# M220p16.net
KiCad netlist of a schematic drawn in EAGLE
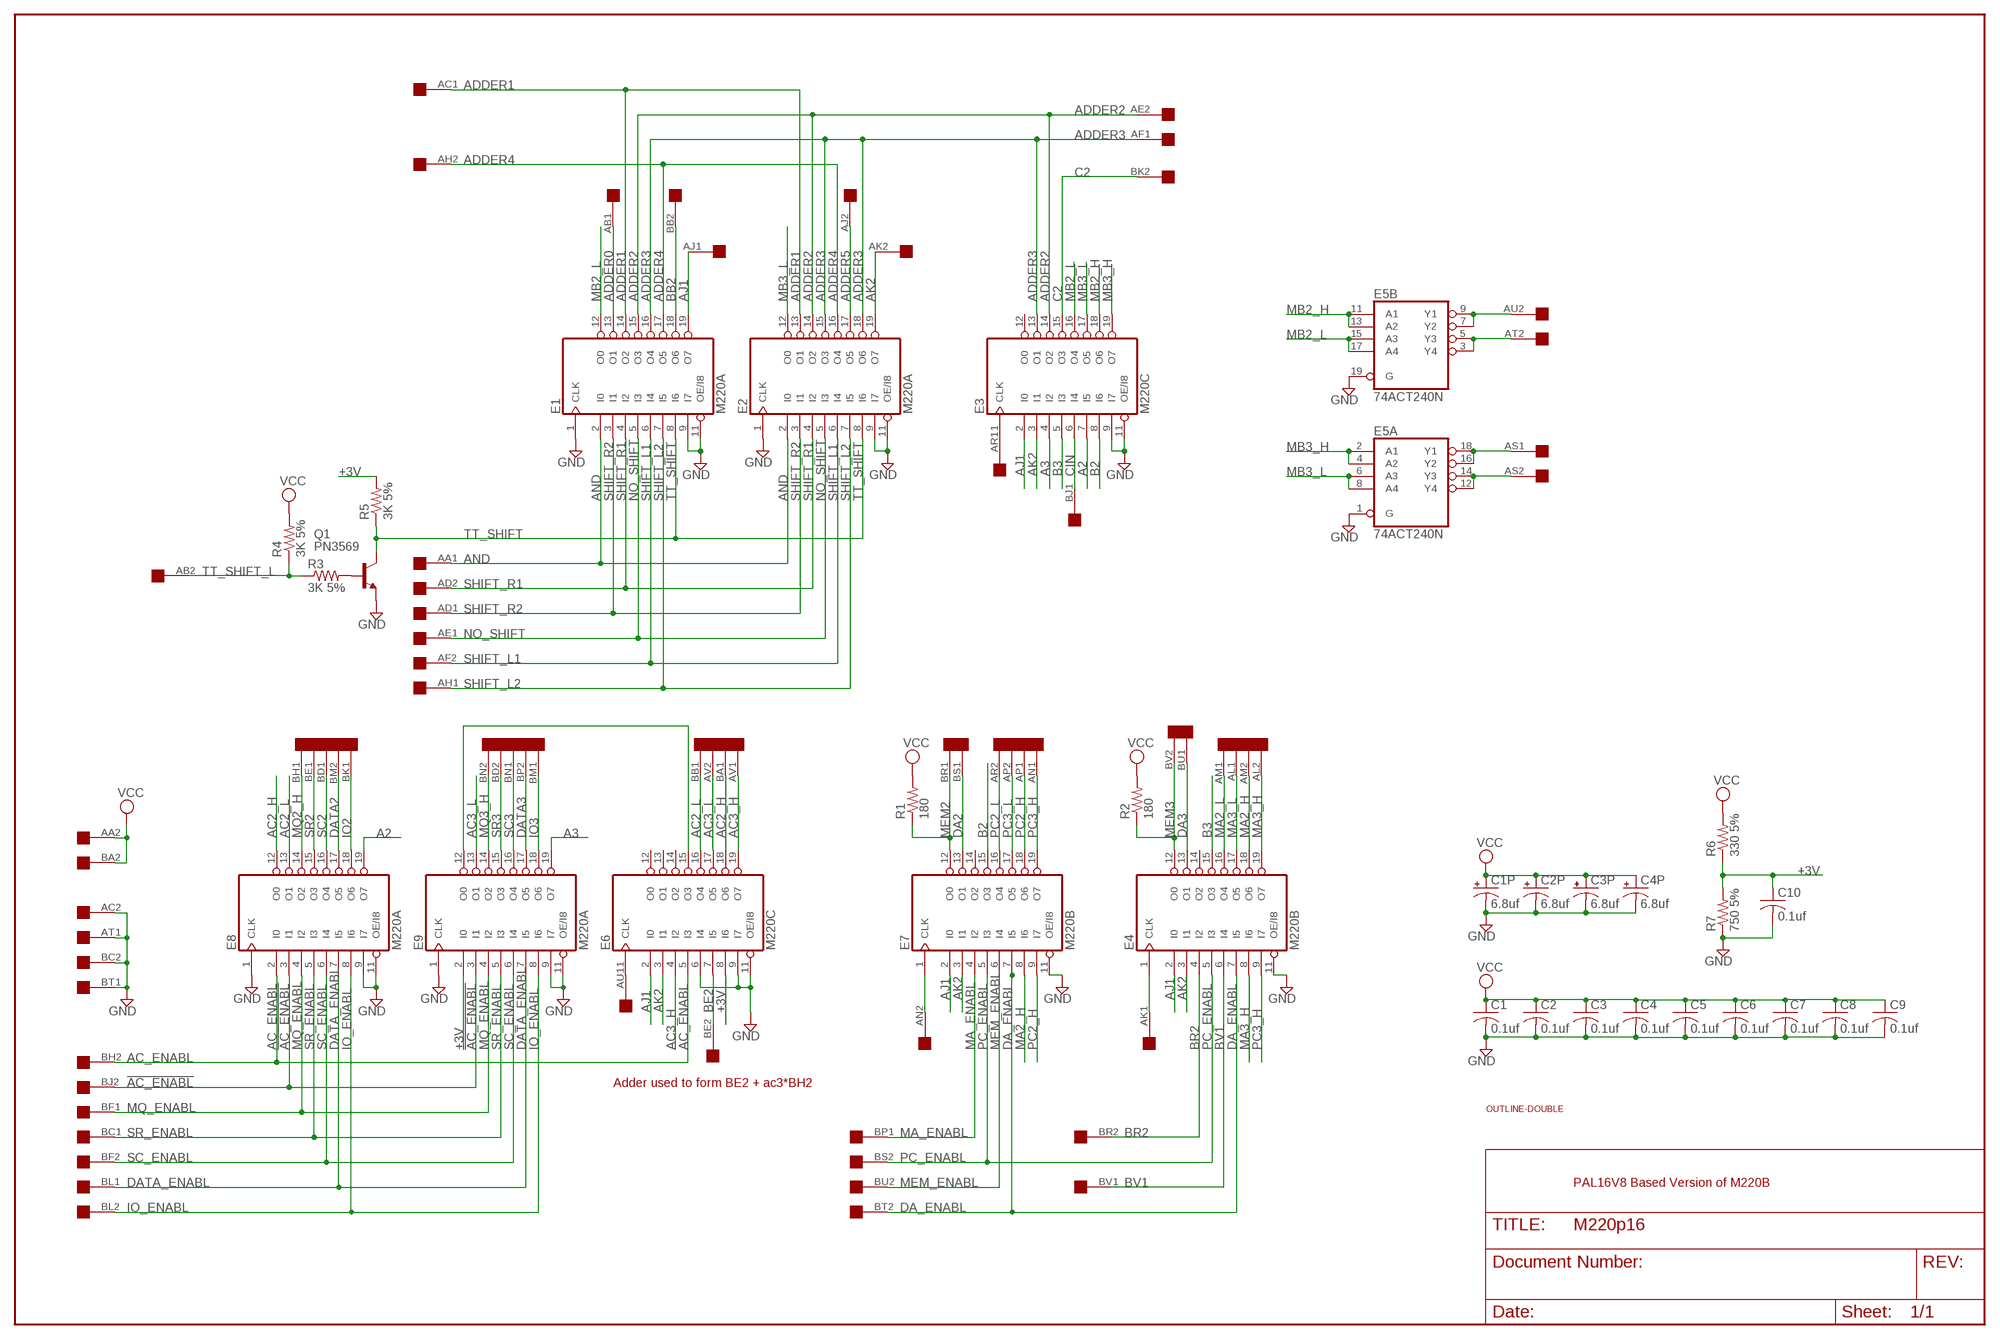
[diagram p0: schematic, sheet 1]

(export (version "E")
  (design (tool "Eeschema 10.0.6"))
  (components
    (comp (ref "C1")
      (value "0.1uf")
      (footprint "eagle-import:C050-025X075")
      (libsource (lib "eagle-import") (part "C-US050-025X075"))
    )
    (comp (ref "C1P")
      (value "6.8uf")
      (footprint "eagle-import:E15-5")
      (libsource (lib "eagle-import") (part "CPOL-USE15-5AXIAL"))
    )
    (comp (ref "C2")
      (value "0.1uf")
      (footprint "eagle-import:C050-025X075")
      (libsource (lib "eagle-import") (part "C-US050-025X075"))
    )
    (comp (ref "C2P")
      (value "6.8uf")
      (footprint "eagle-import:E15-5")
      (libsource (lib "eagle-import") (part "CPOL-USE15-5AXIAL"))
    )
    (comp (ref "C3")
      (value "0.1uf")
      (footprint "eagle-import:C050-025X075")
      (libsource (lib "eagle-import") (part "C-US050-025X075"))
    )
    (comp (ref "C3P")
      (value "6.8uf")
      (footprint "eagle-import:E15-5")
      (libsource (lib "eagle-import") (part "CPOL-USE15-5AXIAL"))
    )
    (comp (ref "C4")
      (value "0.1uf")
      (footprint "eagle-import:C050-025X075")
      (libsource (lib "eagle-import") (part "C-US050-025X075"))
    )
    (comp (ref "C4P")
      (value "6.8uf")
      (footprint "eagle-import:E15-5")
      (libsource (lib "eagle-import") (part "CPOL-USE15-5AXIAL"))
    )
    (comp (ref "C5")
      (value "0.1uf")
      (footprint "eagle-import:C050-025X075")
      (libsource (lib "eagle-import") (part "C-US050-025X075"))
    )
    (comp (ref "C6")
      (value "0.1uf")
      (footprint "eagle-import:C050-025X075")
      (libsource (lib "eagle-import") (part "C-US050-025X075"))
    )
    (comp (ref "C7")
      (value "0.1uf")
      (footprint "eagle-import:C050-025X075")
      (libsource (lib "eagle-import") (part "C-US050-025X075"))
    )
    (comp (ref "C8")
      (value "0.1uf")
      (footprint "eagle-import:C050-025X075")
      (libsource (lib "eagle-import") (part "C-US050-025X075"))
    )
    (comp (ref "C9")
      (value "0.1uf")
      (footprint "eagle-import:C050-025X075")
      (libsource (lib "eagle-import") (part "C-US050-025X075"))
    )
    (comp (ref "C10")
      (value "0.1uf")
      (footprint "eagle-import:C050-025X075")
      (libsource (lib "eagle-import") (part "C-US050-025X075"))
    )
    (comp (ref "E1")
      (value "M220A")
      (footprint "eagle-import:DIL20")
      (fields (field (name "MPN") "GAL16V8D-7LPN"))
      (libsource (lib "eagle-import") (part "16V8"))
    )
    (comp (ref "E2")
      (value "M220A")
      (footprint "eagle-import:DIL20")
      (fields (field (name "MPN") "GAL16V8D-7LPN"))
      (libsource (lib "eagle-import") (part "16V8"))
    )
    (comp (ref "E3")
      (value "M220C")
      (footprint "eagle-import:DIL20")
      (fields (field (name "MPN") "GAL16V8D-7LPN"))
      (libsource (lib "eagle-import") (part "16V8"))
    )
    (comp (ref "E4")
      (value "M220B")
      (footprint "eagle-import:DIL20")
      (fields (field (name "MPN") "GAL16V8D-7LPN"))
      (libsource (lib "eagle-import") (part "16V8"))
    )
    (comp (ref "E5")
      (value "74ACT240N")
      (footprint "eagle-import:DIL20")
      (libsource (lib "eagle-import") (part "74240NS"))
    )
    (comp (ref "E6")
      (value "M220C")
      (footprint "eagle-import:DIL20")
      (fields (field (name "MPN") "GAL16V8D-7LPN"))
      (libsource (lib "eagle-import") (part "16V8"))
    )
    (comp (ref "E7")
      (value "M220B")
      (footprint "eagle-import:DIL20")
      (fields (field (name "MPN") "GAL16V8D-7LPN"))
      (libsource (lib "eagle-import") (part "16V8"))
    )
    (comp (ref "E8")
      (value "M220A")
      (footprint "eagle-import:DIL20")
      (fields (field (name "MPN") "GAL16V8D-7LPN"))
      (libsource (lib "eagle-import") (part "16V8"))
    )
    (comp (ref "E9")
      (value "M220A")
      (footprint "eagle-import:DIL20")
      (fields (field (name "MPN") "GAL16V8D-7LPN"))
      (libsource (lib "eagle-import") (part "16V8"))
    )
    (comp (ref "Q1")
      (value "PN3569")
      (footprint "eagle-import:TO5")
      (libsource (lib "eagle-import") (part "2N2102"))
    )
    (comp (ref "R1")
      (value "180")
      (footprint "eagle-import:0207_10")
      (libsource (lib "eagle-import") (part "R-US_0207/10"))
    )
    (comp (ref "R2")
      (value "180")
      (footprint "eagle-import:0207_10")
      (libsource (lib "eagle-import") (part "R-US_0207/10"))
    )
    (comp (ref "R3")
      (value "3K 5%")
      (footprint "eagle-import:0207_10")
      (libsource (lib "eagle-import") (part "R-US_0207/10"))
    )
    (comp (ref "R4")
      (value "3K 5%")
      (footprint "eagle-import:0207_10")
      (libsource (lib "eagle-import") (part "R-US_0207/10"))
    )
    (comp (ref "R5")
      (value "3K 5%")
      (footprint "eagle-import:0207_10")
      (libsource (lib "eagle-import") (part "R-US_0207/10"))
    )
    (comp (ref "R6")
      (value "330 5%")
      (footprint "eagle-import:0207_10")
      (libsource (lib "eagle-import") (part "R-US_0207/10"))
    )
    (comp (ref "R7")
      (value "750 5%")
      (footprint "eagle-import:0207_10")
      (libsource (lib "eagle-import") (part "R-US_0207/10"))
    )
    (comp (ref "U$1")
      (value "DOUBLE")
      (footprint "eagle-import:EDGE-CON4")
      (libsource (lib "eagle-import") (part "DOUBLE"))
    )
    (comp (ref "U$2")
      (value "OUTLINE-DOUBLE")
      (footprint "eagle-import:DOUBLE")
      (libsource (lib "eagle-import") (part "OUTLINE-DOUBLE"))
    )
  )
  (nets
    (net (code "1") (name "/+3V") (class "Default")
      (node (ref "C10") (pin "1") (pinfunction "1_1") (pintype "passive"))
      (node (ref "E6") (pin "8") (pinfunction "I6_8") (pintype "input"))
      (node (ref "E9") (pin "2") (pinfunction "I0_2") (pintype "input"))
      (node (ref "R5") (pin "2") (pinfunction "2_2") (pintype "passive"))
      (node (ref "R6") (pin "1") (pinfunction "1_1") (pintype "passive"))
      (node (ref "R7") (pin "2") (pinfunction "2_2") (pintype "passive"))
    )
    (net (code "2") (name "/A2") (class "Default")
      (node (ref "E3") (pin "7") (pinfunction "I5_7") (pintype "input"))
      (node (ref "E8") (pin "19") (pinfunction "O7_19") (pintype "bidirectional"))
    )
    (net (code "3") (name "/A3") (class "Default")
      (node (ref "E3") (pin "4") (pinfunction "I2_4") (pintype "input"))
      (node (ref "E9") (pin "19") (pinfunction "O7_19") (pintype "bidirectional"))
    )
    (net (code "4") (name "/AC2_H") (class "Default")
      (node (ref "E6") (pin "18") (pinfunction "O6_18") (pintype "bidirectional"))
      (node (ref "E8") (pin "12") (pinfunction "O0_12") (pintype "bidirectional"))
      (node (ref "U$1") (pin "BA1") (pinfunction "1_BA1") (pintype "bidirectional"))
    )
    (net (code "5") (name "/AC2_L") (class "Default")
      (node (ref "E6") (pin "16") (pinfunction "O4_16") (pintype "bidirectional"))
      (node (ref "E8") (pin "13") (pinfunction "O1_13") (pintype "bidirectional"))
      (node (ref "U$1") (pin "BB1") (pinfunction "1_BB1") (pintype "bidirectional"))
    )
    (net (code "6") (name "/AC3_H") (class "Default")
      (node (ref "E6") (pin "19") (pinfunction "O7_19") (pintype "bidirectional"))
      (node (ref "E6") (pin "4") (pinfunction "I2_4") (pintype "input"))
      (node (ref "U$1") (pin "AV1") (pinfunction "1_AV1") (pintype "bidirectional"))
    )
    (net (code "7") (name "/AC3_L") (class "Default")
      (node (ref "E6") (pin "17") (pinfunction "O5_17") (pintype "bidirectional"))
      (node (ref "E9") (pin "13") (pinfunction "O1_13") (pintype "bidirectional"))
      (node (ref "U$1") (pin "AV2") (pinfunction "1_AV2") (pintype "bidirectional"))
    )
    (net (code "8") (name "/AC_ENABL") (class "Default")
      (node (ref "E6") (pin "5") (pinfunction "I3_5") (pintype "input"))
      (node (ref "E8") (pin "2") (pinfunction "I0_2") (pintype "input"))
      (node (ref "U$1") (pin "BH2") (pinfunction "1_BH2") (pintype "bidirectional"))
    )
    (net (code "9") (name "/ADDER0") (class "Default")
      (node (ref "E1") (pin "13") (pinfunction "O1_13") (pintype "bidirectional"))
      (node (ref "U$1") (pin "AB1") (pinfunction "1_AB1") (pintype "bidirectional"))
    )
    (net (code "10") (name "/ADDER1") (class "Default")
      (node (ref "E1") (pin "14") (pinfunction "O2_14") (pintype "bidirectional"))
      (node (ref "E2") (pin "13") (pinfunction "O1_13") (pintype "bidirectional"))
      (node (ref "U$1") (pin "AC1") (pinfunction "1_AC1") (pintype "bidirectional"))
    )
    (net (code "11") (name "/ADDER2") (class "Default")
      (node (ref "E1") (pin "15") (pinfunction "O3_15") (pintype "bidirectional"))
      (node (ref "E2") (pin "14") (pinfunction "O2_14") (pintype "bidirectional"))
      (node (ref "E3") (pin "14") (pinfunction "O2_14") (pintype "bidirectional"))
      (node (ref "U$1") (pin "AE2") (pinfunction "1_AE2") (pintype "bidirectional"))
    )
    (net (code "12") (name "/ADDER3") (class "Default")
      (node (ref "E1") (pin "16") (pinfunction "O4_16") (pintype "bidirectional"))
      (node (ref "E2") (pin "15") (pinfunction "O3_15") (pintype "bidirectional"))
      (node (ref "E2") (pin "18") (pinfunction "O6_18") (pintype "bidirectional"))
      (node (ref "E3") (pin "13") (pinfunction "O1_13") (pintype "bidirectional"))
      (node (ref "U$1") (pin "AF1") (pinfunction "1_AF1") (pintype "bidirectional"))
    )
    (net (code "13") (name "/ADDER4") (class "Default")
      (node (ref "E1") (pin "17") (pinfunction "O5_17") (pintype "bidirectional"))
      (node (ref "E2") (pin "16") (pinfunction "O4_16") (pintype "bidirectional"))
      (node (ref "U$1") (pin "AH2") (pinfunction "1_AH2") (pintype "bidirectional"))
    )
    (net (code "14") (name "/ADDER5") (class "Default")
      (node (ref "E2") (pin "17") (pinfunction "O5_17") (pintype "bidirectional"))
      (node (ref "U$1") (pin "AJ2") (pinfunction "1_AJ2") (pintype "bidirectional"))
    )
    (net (code "15") (name "/AJ1") (class "Default")
      (node (ref "E1") (pin "19") (pinfunction "O7_19") (pintype "bidirectional"))
      (node (ref "E3") (pin "2") (pinfunction "I0_2") (pintype "input"))
      (node (ref "E4") (pin "2") (pinfunction "I0_2") (pintype "input"))
      (node (ref "E6") (pin "2") (pinfunction "I0_2") (pintype "input"))
      (node (ref "E7") (pin "2") (pinfunction "I0_2") (pintype "input"))
      (node (ref "U$1") (pin "AJ1") (pinfunction "1_AJ1") (pintype "bidirectional"))
    )
    (net (code "16") (name "/AK2") (class "Default")
      (node (ref "E2") (pin "19") (pinfunction "O7_19") (pintype "bidirectional"))
      (node (ref "E3") (pin "3") (pinfunction "I1_3") (pintype "input"))
      (node (ref "E4") (pin "3") (pinfunction "I1_3") (pintype "input"))
      (node (ref "E6") (pin "3") (pinfunction "I1_3") (pintype "input"))
      (node (ref "E7") (pin "3") (pinfunction "I1_3") (pintype "input"))
      (node (ref "U$1") (pin "AK2") (pinfunction "1_AK2") (pintype "bidirectional"))
    )
    (net (code "17") (name "/AND") (class "Default")
      (node (ref "E1") (pin "2") (pinfunction "I0_2") (pintype "input"))
      (node (ref "E2") (pin "2") (pinfunction "I0_2") (pintype "input"))
      (node (ref "U$1") (pin "AA1") (pinfunction "1_AA1") (pintype "bidirectional"))
    )
    (net (code "18") (name "/B2") (class "Default")
      (node (ref "E3") (pin "8") (pinfunction "I6_8") (pintype "input"))
      (node (ref "E7") (pin "15") (pinfunction "O3_15") (pintype "bidirectional"))
    )
    (net (code "19") (name "/B3") (class "Default")
      (node (ref "E3") (pin "5") (pinfunction "I3_5") (pintype "input"))
      (node (ref "E4") (pin "15") (pinfunction "O3_15") (pintype "bidirectional"))
    )
    (net (code "20") (name "/BB2") (class "Default")
      (node (ref "E1") (pin "18") (pinfunction "O6_18") (pintype "bidirectional"))
      (node (ref "U$1") (pin "BB2") (pinfunction "1_BB2") (pintype "bidirectional"))
    )
    (net (code "21") (name "/BE2") (class "Default")
      (node (ref "E6") (pin "7") (pinfunction "I5_7") (pintype "input"))
      (node (ref "U$1") (pin "BE2") (pinfunction "1_BE2") (pintype "bidirectional"))
    )
    (net (code "22") (name "/BR2") (class "Default")
      (node (ref "E4") (pin "4") (pinfunction "I2_4") (pintype "input"))
      (node (ref "U$1") (pin "BR2") (pinfunction "1_BR2") (pintype "bidirectional"))
    )
    (net (code "23") (name "/BV1") (class "Default")
      (node (ref "E4") (pin "6") (pinfunction "I4_6") (pintype "input"))
      (node (ref "U$1") (pin "BV1") (pinfunction "1_BV1") (pintype "bidirectional"))
    )
    (net (code "24") (name "/C2") (class "Default")
      (node (ref "E3") (pin "15") (pinfunction "O3_15") (pintype "bidirectional"))
      (node (ref "U$1") (pin "BK2") (pinfunction "1_BK2") (pintype "bidirectional"))
    )
    (net (code "25") (name "/CIN") (class "Default")
      (node (ref "E3") (pin "6") (pinfunction "I4_6") (pintype "input"))
      (node (ref "U$1") (pin "BJ1") (pinfunction "1_BJ1") (pintype "bidirectional"))
    )
    (net (code "26") (name "/DA2") (class "Default")
      (node (ref "E7") (pin "13") (pinfunction "O1_13") (pintype "bidirectional"))
      (node (ref "U$1") (pin "BS1") (pinfunction "1_BS1") (pintype "bidirectional"))
    )
    (net (code "27") (name "/DA3") (class "Default")
      (node (ref "E4") (pin "13") (pinfunction "O1_13") (pintype "bidirectional"))
      (node (ref "U$1") (pin "BU1") (pinfunction "1_BU1") (pintype "bidirectional"))
    )
    (net (code "28") (name "/DATA2") (class "Default")
      (node (ref "E8") (pin "17") (pinfunction "O5_17") (pintype "bidirectional"))
      (node (ref "U$1") (pin "BM2") (pinfunction "1_BM2") (pintype "bidirectional"))
    )
    (net (code "29") (name "/DATA3") (class "Default")
      (node (ref "E9") (pin "17") (pinfunction "O5_17") (pintype "bidirectional"))
      (node (ref "U$1") (pin "BP2") (pinfunction "1_BP2") (pintype "bidirectional"))
    )
    (net (code "30") (name "/DATA_ENABL") (class "Default")
      (node (ref "E8") (pin "7") (pinfunction "I5_7") (pintype "input"))
      (node (ref "E9") (pin "7") (pinfunction "I5_7") (pintype "input"))
      (node (ref "U$1") (pin "BL1") (pinfunction "1_BL1") (pintype "bidirectional"))
    )
    (net (code "31") (name "/DA_ENABL") (class "Default")
      (node (ref "E4") (pin "7") (pinfunction "I5_7") (pintype "input"))
      (node (ref "E7") (pin "7") (pinfunction "I5_7") (pintype "input"))
      (node (ref "U$1") (pin "BT2") (pinfunction "1_BT2") (pintype "bidirectional"))
    )
    (net (code "32") (name "/IO2") (class "Default")
      (node (ref "E8") (pin "18") (pinfunction "O6_18") (pintype "bidirectional"))
      (node (ref "U$1") (pin "BK1") (pinfunction "1_BK1") (pintype "bidirectional"))
    )
    (net (code "33") (name "/IO3") (class "Default")
      (node (ref "E9") (pin "18") (pinfunction "O6_18") (pintype "bidirectional"))
      (node (ref "U$1") (pin "BM1") (pinfunction "1_BM1") (pintype "bidirectional"))
    )
    (net (code "34") (name "/IO_ENABL") (class "Default")
      (node (ref "E8") (pin "8") (pinfunction "I6_8") (pintype "input"))
      (node (ref "E9") (pin "8") (pinfunction "I6_8") (pintype "input"))
      (node (ref "U$1") (pin "BL2") (pinfunction "1_BL2") (pintype "bidirectional"))
    )
    (net (code "35") (name "/MA2_H") (class "Default")
      (node (ref "E4") (pin "18") (pinfunction "O6_18") (pintype "bidirectional"))
      (node (ref "E7") (pin "8") (pinfunction "I6_8") (pintype "input"))
      (node (ref "U$1") (pin "AM2") (pinfunction "1_AM2") (pintype "bidirectional"))
    )
    (net (code "36") (name "/MA2_L") (class "Default")
      (node (ref "E4") (pin "16") (pinfunction "O4_16") (pintype "bidirectional"))
      (node (ref "U$1") (pin "AM1") (pinfunction "1_AM1") (pintype "bidirectional"))
    )
    (net (code "37") (name "/MA3_H") (class "Default")
      (node (ref "E4") (pin "19") (pinfunction "O7_19") (pintype "bidirectional"))
      (node (ref "E4") (pin "8") (pinfunction "I6_8") (pintype "input"))
      (node (ref "U$1") (pin "AL2") (pinfunction "1_AL2") (pintype "bidirectional"))
    )
    (net (code "38") (name "/MA3_L") (class "Default")
      (node (ref "E4") (pin "17") (pinfunction "O5_17") (pintype "bidirectional"))
      (node (ref "U$1") (pin "AL1") (pinfunction "1_AL1") (pintype "bidirectional"))
    )
    (net (code "39") (name "/MA_ENABL") (class "Default")
      (node (ref "E7") (pin "4") (pinfunction "I2_4") (pintype "input"))
      (node (ref "U$1") (pin "BP1") (pinfunction "1_BP1") (pintype "bidirectional"))
    )
    (net (code "40") (name "/MB2_H") (class "Default")
      (node (ref "E3") (pin "18") (pinfunction "O6_18") (pintype "bidirectional"))
      (node (ref "E5") (pin "11") (pinfunction "A1_11") (pintype "input"))
      (node (ref "E5") (pin "13") (pinfunction "A2_13") (pintype "input"))
    )
    (net (code "41") (name "/MB2_L") (class "Default")
      (node (ref "E1") (pin "12") (pinfunction "O0_12") (pintype "bidirectional"))
      (node (ref "E3") (pin "16") (pinfunction "O4_16") (pintype "bidirectional"))
      (node (ref "E5") (pin "15") (pinfunction "A3_15") (pintype "input"))
      (node (ref "E5") (pin "17") (pinfunction "A4_17") (pintype "input"))
    )
    (net (code "42") (name "/MB3_H") (class "Default")
      (node (ref "E3") (pin "19") (pinfunction "O7_19") (pintype "bidirectional"))
      (node (ref "E5") (pin "2") (pinfunction "A1_2") (pintype "input"))
      (node (ref "E5") (pin "4") (pinfunction "A2_4") (pintype "input"))
    )
    (net (code "43") (name "/MB3_L") (class "Default")
      (node (ref "E2") (pin "12") (pinfunction "O0_12") (pintype "bidirectional"))
      (node (ref "E3") (pin "17") (pinfunction "O5_17") (pintype "bidirectional"))
      (node (ref "E5") (pin "6") (pinfunction "A3_6") (pintype "input"))
      (node (ref "E5") (pin "8") (pinfunction "A4_8") (pintype "input"))
    )
    (net (code "44") (name "/MEM2") (class "Default")
      (node (ref "E7") (pin "12") (pinfunction "O0_12") (pintype "bidirectional"))
      (node (ref "R1") (pin "1") (pinfunction "1_1") (pintype "passive"))
      (node (ref "U$1") (pin "BR1") (pinfunction "1_BR1") (pintype "bidirectional"))
    )
    (net (code "45") (name "/MEM3") (class "Default")
      (node (ref "E4") (pin "12") (pinfunction "O0_12") (pintype "bidirectional"))
      (node (ref "R2") (pin "1") (pinfunction "1_1") (pintype "passive"))
      (node (ref "U$1") (pin "BV2") (pinfunction "1_BV2") (pintype "bidirectional"))
    )
    (net (code "46") (name "/MEM_ENABL") (class "Default")
      (node (ref "E7") (pin "6") (pinfunction "I4_6") (pintype "input"))
      (node (ref "U$1") (pin "BU2") (pinfunction "1_BU2") (pintype "bidirectional"))
    )
    (net (code "47") (name "/MQ2_H") (class "Default")
      (node (ref "E8") (pin "14") (pinfunction "O2_14") (pintype "bidirectional"))
      (node (ref "U$1") (pin "BH1") (pinfunction "1_BH1") (pintype "bidirectional"))
    )
    (net (code "48") (name "/MQ3_H") (class "Default")
      (node (ref "E9") (pin "14") (pinfunction "O2_14") (pintype "bidirectional"))
      (node (ref "U$1") (pin "BN2") (pinfunction "1_BN2") (pintype "bidirectional"))
    )
    (net (code "49") (name "/MQ_ENABL") (class "Default")
      (node (ref "E8") (pin "4") (pinfunction "I2_4") (pintype "input"))
      (node (ref "E9") (pin "4") (pinfunction "I2_4") (pintype "input"))
      (node (ref "U$1") (pin "BF1") (pinfunction "1_BF1") (pintype "bidirectional"))
    )
    (net (code "50") (name "/NO_SHIFT") (class "Default")
      (node (ref "E1") (pin "5") (pinfunction "I3_5") (pintype "input"))
      (node (ref "E2") (pin "5") (pinfunction "I3_5") (pintype "input"))
      (node (ref "U$1") (pin "AE1") (pinfunction "1_AE1") (pintype "bidirectional"))
    )
    (net (code "51") (name "/PC2_H") (class "Default")
      (node (ref "E7") (pin "18") (pinfunction "O6_18") (pintype "bidirectional"))
      (node (ref "E7") (pin "9") (pinfunction "I7_9") (pintype "input"))
      (node (ref "U$1") (pin "AP1") (pinfunction "1_AP1") (pintype "bidirectional"))
    )
    (net (code "52") (name "/PC2_L") (class "Default")
      (node (ref "E7") (pin "16") (pinfunction "O4_16") (pintype "bidirectional"))
      (node (ref "U$1") (pin "AR2") (pinfunction "1_AR2") (pintype "bidirectional"))
    )
    (net (code "53") (name "/PC3_H") (class "Default")
      (node (ref "E4") (pin "9") (pinfunction "I7_9") (pintype "input"))
      (node (ref "E7") (pin "19") (pinfunction "O7_19") (pintype "bidirectional"))
      (node (ref "U$1") (pin "AN1") (pinfunction "1_AN1") (pintype "bidirectional"))
    )
    (net (code "54") (name "/PC3_L") (class "Default")
      (node (ref "E7") (pin "17") (pinfunction "O5_17") (pintype "bidirectional"))
      (node (ref "U$1") (pin "AP2") (pinfunction "1_AP2") (pintype "bidirectional"))
    )
    (net (code "55") (name "/PC_ENABL") (class "Default")
      (node (ref "E4") (pin "5") (pinfunction "I3_5") (pintype "input"))
      (node (ref "E7") (pin "5") (pinfunction "I3_5") (pintype "input"))
      (node (ref "U$1") (pin "BS2") (pinfunction "1_BS2") (pintype "bidirectional"))
    )
    (net (code "56") (name "/SC2") (class "Default")
      (node (ref "E8") (pin "16") (pinfunction "O4_16") (pintype "bidirectional"))
      (node (ref "U$1") (pin "BD1") (pinfunction "1_BD1") (pintype "bidirectional"))
    )
    (net (code "57") (name "/SC3") (class "Default")
      (node (ref "E9") (pin "16") (pinfunction "O4_16") (pintype "bidirectional"))
      (node (ref "U$1") (pin "BN1") (pinfunction "1_BN1") (pintype "bidirectional"))
    )
    (net (code "58") (name "/SC_ENABL") (class "Default")
      (node (ref "E8") (pin "6") (pinfunction "I4_6") (pintype "input"))
      (node (ref "E9") (pin "6") (pinfunction "I4_6") (pintype "input"))
      (node (ref "U$1") (pin "BF2") (pinfunction "1_BF2") (pintype "bidirectional"))
    )
    (net (code "59") (name "/SHIFT_L1") (class "Default")
      (node (ref "E1") (pin "6") (pinfunction "I4_6") (pintype "input"))
      (node (ref "E2") (pin "6") (pinfunction "I4_6") (pintype "input"))
      (node (ref "U$1") (pin "AF2") (pinfunction "1_AF2") (pintype "bidirectional"))
    )
    (net (code "60") (name "/SHIFT_L2") (class "Default")
      (node (ref "E1") (pin "7") (pinfunction "I5_7") (pintype "input"))
      (node (ref "E2") (pin "7") (pinfunction "I5_7") (pintype "input"))
      (node (ref "U$1") (pin "AH1") (pinfunction "1_AH1") (pintype "bidirectional"))
    )
    (net (code "61") (name "/SHIFT_R1") (class "Default")
      (node (ref "E1") (pin "4") (pinfunction "I2_4") (pintype "input"))
      (node (ref "E2") (pin "4") (pinfunction "I2_4") (pintype "input"))
      (node (ref "U$1") (pin "AD2") (pinfunction "1_AD2") (pintype "bidirectional"))
    )
    (net (code "62") (name "/SHIFT_R2") (class "Default")
      (node (ref "E1") (pin "3") (pinfunction "I1_3") (pintype "input"))
      (node (ref "E2") (pin "3") (pinfunction "I1_3") (pintype "input"))
      (node (ref "U$1") (pin "AD1") (pinfunction "1_AD1") (pintype "bidirectional"))
    )
    (net (code "63") (name "/SR2") (class "Default")
      (node (ref "E8") (pin "15") (pinfunction "O3_15") (pintype "bidirectional"))
      (node (ref "U$1") (pin "BE1") (pinfunction "1_BE1") (pintype "bidirectional"))
    )
    (net (code "64") (name "/SR3") (class "Default")
      (node (ref "E9") (pin "15") (pinfunction "O3_15") (pintype "bidirectional"))
      (node (ref "U$1") (pin "BD2") (pinfunction "1_BD2") (pintype "bidirectional"))
    )
    (net (code "65") (name "/SR_ENABL") (class "Default")
      (node (ref "E8") (pin "5") (pinfunction "I3_5") (pintype "input"))
      (node (ref "E9") (pin "5") (pinfunction "I3_5") (pintype "input"))
      (node (ref "U$1") (pin "BC1") (pinfunction "1_BC1") (pintype "bidirectional"))
    )
    (net (code "66") (name "/TT_SHIFT") (class "Default")
      (node (ref "E1") (pin "8") (pinfunction "I6_8") (pintype "input"))
      (node (ref "E2") (pin "8") (pinfunction "I6_8") (pintype "input"))
      (node (ref "Q1") (pin "3") (pinfunction "C_3") (pintype "passive"))
      (node (ref "R5") (pin "1") (pinfunction "1_1") (pintype "passive"))
    )
    (net (code "67") (name "/TT_SHIFT_L") (class "Default")
      (node (ref "R3") (pin "1") (pinfunction "1_1") (pintype "passive"))
      (node (ref "R4") (pin "1") (pinfunction "1_1") (pintype "passive"))
      (node (ref "U$1") (pin "AB2") (pinfunction "1_AB2") (pintype "bidirectional"))
    )
    (net (code "68") (name "/~{AC_ENABL}") (class "Default")
      (node (ref "E8") (pin "3") (pinfunction "I1_3") (pintype "input"))
      (node (ref "E9") (pin "3") (pinfunction "I1_3") (pintype "input"))
      (node (ref "U$1") (pin "BJ2") (pinfunction "1_BJ2") (pintype "bidirectional"))
    )
    (net (code "69") (name "GND") (class "Default")
      (node (ref "C1") (pin "2") (pinfunction "2_2") (pintype "passive"))
      (node (ref "C10") (pin "2") (pinfunction "2_2") (pintype "passive"))
      (node (ref "C1P") (pin "-") (pinfunction "-_-") (pintype "passive"))
      (node (ref "C2") (pin "2") (pinfunction "2_2") (pintype "passive"))
      (node (ref "C2P") (pin "-") (pinfunction "-_-") (pintype "passive"))
      (node (ref "C3") (pin "2") (pinfunction "2_2") (pintype "passive"))
      (node (ref "C3P") (pin "-") (pinfunction "-_-") (pintype "passive"))
      (node (ref "C4") (pin "2") (pinfunction "2_2") (pintype "passive"))
      (node (ref "C4P") (pin "-") (pinfunction "-_-") (pintype "passive"))
      (node (ref "C5") (pin "2") (pinfunction "2_2") (pintype "passive"))
      (node (ref "C6") (pin "2") (pinfunction "2_2") (pintype "passive"))
      (node (ref "C7") (pin "2") (pinfunction "2_2") (pintype "passive"))
      (node (ref "C8") (pin "2") (pinfunction "2_2") (pintype "passive"))
      (node (ref "C9") (pin "2") (pinfunction "2_2") (pintype "passive"))
      (node (ref "E1") (pin "1") (pinfunction "CLK_1") (pintype "input"))
      (node (ref "E1") (pin "11") (pinfunction "OE/I8_11") (pintype "input"))
      (node (ref "E1") (pin "9") (pinfunction "I7_9") (pintype "input"))
      (node (ref "E2") (pin "1") (pinfunction "CLK_1") (pintype "input"))
      (node (ref "E2") (pin "11") (pinfunction "OE/I8_11") (pintype "input"))
      (node (ref "E2") (pin "9") (pinfunction "I7_9") (pintype "input"))
      (node (ref "E3") (pin "11") (pinfunction "OE/I8_11") (pintype "input"))
      (node (ref "E3") (pin "9") (pinfunction "I7_9") (pintype "input"))
      (node (ref "E4") (pin "11") (pinfunction "OE/I8_11") (pintype "input"))
      (node (ref "E5") (pin "1") (pinfunction "G_1") (pintype "input"))
      (node (ref "E5") (pin "19") (pinfunction "G_19") (pintype "input"))
      (node (ref "E6") (pin "11") (pinfunction "OE/I8_11") (pintype "input"))
      (node (ref "E6") (pin "6") (pinfunction "I4_6") (pintype "input"))
      (node (ref "E6") (pin "9") (pinfunction "I7_9") (pintype "input"))
      (node (ref "E7") (pin "11") (pinfunction "OE/I8_11") (pintype "input"))
      (node (ref "E8") (pin "1") (pinfunction "CLK_1") (pintype "input"))
      (node (ref "E8") (pin "11") (pinfunction "OE/I8_11") (pintype "input"))
      (node (ref "E8") (pin "9") (pinfunction "I7_9") (pintype "input"))
      (node (ref "E9") (pin "1") (pinfunction "CLK_1") (pintype "input"))
      (node (ref "E9") (pin "11") (pinfunction "OE/I8_11") (pintype "input"))
      (node (ref "E9") (pin "9") (pinfunction "I7_9") (pintype "input"))
      (node (ref "Q1") (pin "1") (pinfunction "E_1") (pintype "passive"))
      (node (ref "R7") (pin "1") (pinfunction "1_1") (pintype "passive"))
      (node (ref "U$1") (pin "AC2") (pinfunction "1_AC2") (pintype "bidirectional"))
      (node (ref "U$1") (pin "AT1") (pinfunction "1_AT1") (pintype "bidirectional"))
      (node (ref "U$1") (pin "BC2") (pinfunction "1_BC2") (pintype "bidirectional"))
      (node (ref "U$1") (pin "BT1") (pinfunction "1_BT1") (pintype "bidirectional"))
    )
    (net (code "70") (name "Net-(E3A-CLK)") (class "Default")
      (node (ref "E3") (pin "1") (pinfunction "CLK_1") (pintype "input"))
      (node (ref "U$1") (pin "AR1") (pinfunction "1_AR1") (pintype "bidirectional"))
    )
    (net (code "71") (name "Net-(E4A-CLK)") (class "Default")
      (node (ref "E4") (pin "1") (pinfunction "CLK_1") (pintype "input"))
      (node (ref "U$1") (pin "AK1") (pinfunction "1_AK1") (pintype "bidirectional"))
    )
    (net (code "72") (name "Net-(E5A-Y1)") (class "Default")
      (node (ref "E5") (pin "16") (pinfunction "Y2_16") (pintype "tri_state"))
      (node (ref "E5") (pin "18") (pinfunction "Y1_18") (pintype "tri_state"))
      (node (ref "U$1") (pin "AS1") (pinfunction "1_AS1") (pintype "bidirectional"))
    )
    (net (code "73") (name "Net-(E5A-Y3)") (class "Default")
      (node (ref "E5") (pin "12") (pinfunction "Y4_12") (pintype "tri_state"))
      (node (ref "E5") (pin "14") (pinfunction "Y3_14") (pintype "tri_state"))
      (node (ref "U$1") (pin "AS2") (pinfunction "1_AS2") (pintype "bidirectional"))
    )
    (net (code "74") (name "Net-(E5B-Y1)") (class "Default")
      (node (ref "E5") (pin "7") (pinfunction "Y2_7") (pintype "tri_state"))
      (node (ref "E5") (pin "9") (pinfunction "Y1_9") (pintype "tri_state"))
      (node (ref "U$1") (pin "AU2") (pinfunction "1_AU2") (pintype "bidirectional"))
    )
    (net (code "75") (name "Net-(E5B-Y3)") (class "Default")
      (node (ref "E5") (pin "3") (pinfunction "Y4_3") (pintype "tri_state"))
      (node (ref "E5") (pin "5") (pinfunction "Y3_5") (pintype "tri_state"))
      (node (ref "U$1") (pin "AT2") (pinfunction "1_AT2") (pintype "bidirectional"))
    )
    (net (code "76") (name "Net-(E6A-CLK)") (class "Default")
      (node (ref "E6") (pin "1") (pinfunction "CLK_1") (pintype "input"))
      (node (ref "U$1") (pin "AU1") (pinfunction "1_AU1") (pintype "bidirectional"))
    )
    (net (code "77") (name "Net-(E6A-O3)") (class "Default")
      (node (ref "E6") (pin "15") (pinfunction "O3_15") (pintype "bidirectional"))
      (node (ref "E9") (pin "12") (pinfunction "O0_12") (pintype "bidirectional"))
    )
    (net (code "78") (name "Net-(E7A-CLK)") (class "Default")
      (node (ref "E7") (pin "1") (pinfunction "CLK_1") (pintype "input"))
      (node (ref "U$1") (pin "AN2") (pinfunction "1_AN2") (pintype "bidirectional"))
    )
    (net (code "79") (name "Net-(Q1-B)") (class "Default")
      (node (ref "Q1") (pin "2") (pinfunction "B_2") (pintype "passive"))
      (node (ref "R3") (pin "2") (pinfunction "2_2") (pintype "passive"))
    )
    (net (code "80") (name "VCC") (class "Default")
      (node (ref "C1") (pin "1") (pinfunction "1_1") (pintype "passive"))
      (node (ref "C1P") (pin "+") (pinfunction "+_+") (pintype "passive"))
      (node (ref "C2") (pin "1") (pinfunction "1_1") (pintype "passive"))
      (node (ref "C2P") (pin "+") (pinfunction "+_+") (pintype "passive"))
      (node (ref "C3") (pin "1") (pinfunction "1_1") (pintype "passive"))
      (node (ref "C3P") (pin "+") (pinfunction "+_+") (pintype "passive"))
      (node (ref "C4") (pin "1") (pinfunction "1_1") (pintype "passive"))
      (node (ref "C4P") (pin "+") (pinfunction "+_+") (pintype "passive"))
      (node (ref "C5") (pin "1") (pinfunction "1_1") (pintype "passive"))
      (node (ref "C6") (pin "1") (pinfunction "1_1") (pintype "passive"))
      (node (ref "C7") (pin "1") (pinfunction "1_1") (pintype "passive"))
      (node (ref "C8") (pin "1") (pinfunction "1_1") (pintype "passive"))
      (node (ref "C9") (pin "1") (pinfunction "1_1") (pintype "passive"))
      (node (ref "R1") (pin "2") (pinfunction "2_2") (pintype "passive"))
      (node (ref "R2") (pin "2") (pinfunction "2_2") (pintype "passive"))
      (node (ref "R4") (pin "2") (pinfunction "2_2") (pintype "passive"))
      (node (ref "R6") (pin "2") (pinfunction "2_2") (pintype "passive"))
      (node (ref "U$1") (pin "AA2") (pinfunction "1_AA2") (pintype "bidirectional"))
      (node (ref "U$1") (pin "BA2") (pinfunction "1_BA2") (pintype "bidirectional"))
    )
    (net (code "81") (name "unconnected-(E3A-O0-Pad12)") (class "Default")
      (node (ref "E3") (pin "12") (pinfunction "O0_12") (pintype "bidirectional"))
    )
    (net (code "82") (name "unconnected-(E4A-O2-Pad14)") (class "Default")
      (node (ref "E4") (pin "14") (pinfunction "O2_14") (pintype "bidirectional"))
    )
    (net (code "83") (name "unconnected-(E6A-O0-Pad12)") (class "Default")
      (node (ref "E6") (pin "12") (pinfunction "O0_12") (pintype "bidirectional"))
    )
    (net (code "84") (name "unconnected-(E6A-O1-Pad13)") (class "Default")
      (node (ref "E6") (pin "13") (pinfunction "O1_13") (pintype "bidirectional"))
    )
    (net (code "85") (name "unconnected-(E6A-O2-Pad14)") (class "Default")
      (node (ref "E6") (pin "14") (pinfunction "O2_14") (pintype "bidirectional"))
    )
    (net (code "86") (name "unconnected-(E7A-O2-Pad14)") (class "Default")
      (node (ref "E7") (pin "14") (pinfunction "O2_14") (pintype "bidirectional"))
    )
  )
)
